# -MCU.net
KiCad netlist of a schematic drawn in Altium Designer
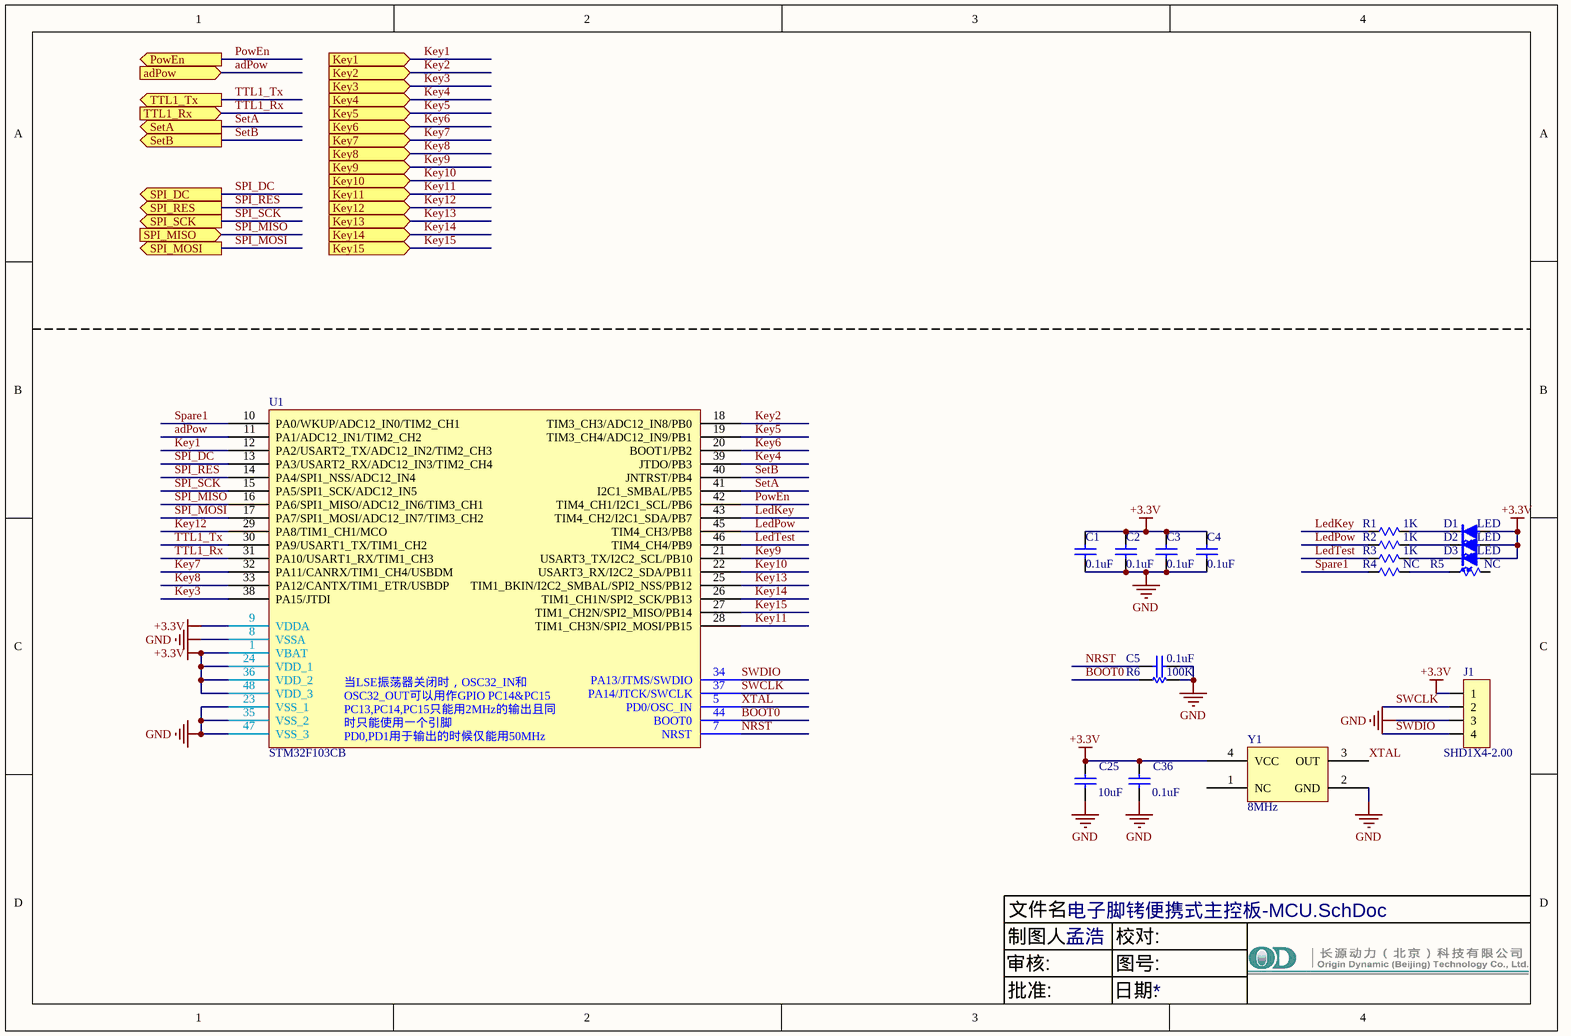
[diagram p0: 电子脚铐便携式主控板-MCU.SchDoc]

(export (version "E")
  (design (tool "Eeschema 10.0.6"))
  (components
    (comp (ref "C1") (value "0.1uF") (footprint "C0603") (libsource (lib "RLCYDF") (part "Cap Semi")))
    (comp (ref "C2") (value "0.1uF") (footprint "C0603") (libsource (lib "RLCYDF") (part "Cap Semi")))
    (comp (ref "C3") (value "0.1uF") (footprint "C0603") (libsource (lib "RLCYDF") (part "Cap Semi")))
    (comp (ref "C4") (value "0.1uF") (footprint "C0603") (libsource (lib "RLCYDF") (part "Cap Semi")))
    (comp (ref "C5") (value "0.1uF") (footprint "C0603") (libsource (lib "RLCYDF") (part "Cap Semi")))
    (comp (ref "C25") (value "10uF") (footprint "C0603") (libsource (lib "RLCYDF") (part "Cap Semi")))
    (comp (ref "C36") (value "0.1uF") (footprint "C0603") (libsource (lib "RLCYDF") (part "Cap Semi")))
    (comp (ref "D1")
      (value "LED")
      (footprint "LED0805")
      (libsource (lib "Passive Components Class") (part "LED"))
    )
    (comp (ref "D2")
      (value "LED")
      (footprint "LED0805")
      (libsource (lib "Passive Components Class") (part "LED"))
    )
    (comp (ref "D3")
      (value "LED")
      (footprint "LED0805")
      (libsource (lib "Passive Components Class") (part "LED"))
    )
    (comp (ref "J1")
      (value "SHD1X4-2.00")
      (footprint "Jk1*4-2.0")
      (libsource (lib "Connector Class") (part "HEADER1X4"))
    )
    (comp (ref "R1")
      (value "1K")
      (footprint "R0603")
      (description "Resistor")
      (fields (field (name "PUBLISHER") "Altium Limited"))
      (libsource (lib "UP-Robot") (part "Res"))
    )
    (comp (ref "R2")
      (value "1K")
      (footprint "R0603")
      (description "Resistor")
      (fields (field (name "PUBLISHER") "Altium Limited"))
      (libsource (lib "UP-Robot") (part "Res"))
    )
    (comp (ref "R3")
      (value "1K")
      (footprint "R0603")
      (description "Resistor")
      (fields (field (name "PUBLISHER") "Altium Limited"))
      (libsource (lib "UP-Robot") (part "Res"))
    )
    (comp (ref "R4")
      (value "NC")
      (footprint "R0603")
      (description "Resistor")
      (fields (field (name "PUBLISHER") "Altium Limited"))
      (libsource (lib "UP-Robot") (part "Res"))
    )
    (comp (ref "R5")
      (value "NC")
      (footprint "R0603")
      (description "Resistor")
      (fields (field (name "PUBLISHER") "Altium Limited"))
      (libsource (lib "UP-Robot") (part "Res"))
    )
    (comp (ref "R6") (value "100K") (footprint "R0603") (libsource (lib "RLCYDF") (part "Res")))
    (comp (ref "U1")
      (value "STM32F103CB")
      (footprint "LQFP48")
      (libsource (lib "stm32") (part "STM32F103Cx"))
    )
    (comp (ref "Y1")
      (value "8MHz")
      (footprint "XTAL5032")
      (description "SM crystal oscilator")
      (libsource (lib "RLCYDF") (part "XTAL"))
    )
  )
  (nets
    (net (code "1") (name "+3.3V") (class "Default")
      (node (ref "C1") (pin "1") (pinfunction "1_1") (pintype "passive"))
      (node (ref "C2") (pin "1") (pinfunction "1_1") (pintype "passive"))
      (node (ref "C25") (pin "2") (pinfunction "2_2") (pintype "passive"))
      (node (ref "C3") (pin "1") (pinfunction "1_1") (pintype "passive"))
      (node (ref "C36") (pin "2") (pinfunction "2_2") (pintype "passive"))
      (node (ref "C4") (pin "1") (pinfunction "1_1") (pintype "passive"))
      (node (ref "D1") (pin "1") (pinfunction "A_1") (pintype "passive"))
      (node (ref "D2") (pin "1") (pinfunction "A_1") (pintype "passive"))
      (node (ref "D3") (pin "1") (pinfunction "A_1") (pintype "passive"))
      (node (ref "J1") (pin "1") (pinfunction "1_1") (pintype "passive"))
      (node (ref "U1") (pin "1") (pinfunction "VBAT_1") (pintype "power_in"))
      (node (ref "U1") (pin "24") (pinfunction "VDD_1_24") (pintype "power_in"))
      (node (ref "U1") (pin "36") (pinfunction "VDD_2_36") (pintype "power_in"))
      (node (ref "U1") (pin "48") (pinfunction "VDD_3_48") (pintype "power_in"))
      (node (ref "U1") (pin "9") (pinfunction "VDDA_9") (pintype "power_in"))
      (node (ref "Y1") (pin "4") (pinfunction "VCC_4") (pintype "passive"))
    )
    (net (code "2") (name "/BOOT0") (class "Default")
      (node (ref "R6") (pin "1") (pinfunction "1_1") (pintype "passive"))
      (node (ref "U1") (pin "44") (pinfunction "BOOT0_44") (pintype "passive"))
    )
    (net (code "3") (name "/Key1") (class "Default")
      (node (ref "U1") (pin "12") (pinfunction "PA2/USART2_TX/ADC12_IN2/TIM2_CH3_12") (pintype "passive"))
    )
    (net (code "4") (name "/Key2") (class "Default")
      (node (ref "U1") (pin "18") (pinfunction "TIM3_CH3/ADC12_IN8/PB0_18") (pintype "passive"))
    )
    (net (code "5") (name "/Key3") (class "Default")
      (node (ref "U1") (pin "38") (pinfunction "PA15/JTDI_38") (pintype "passive"))
    )
    (net (code "6") (name "/Key4") (class "Default")
      (node (ref "U1") (pin "39") (pinfunction "JTDO/PB3_39") (pintype "passive"))
    )
    (net (code "7") (name "/Key5") (class "Default")
      (node (ref "U1") (pin "19") (pinfunction "TIM3_CH4/ADC12_IN9/PB1_19") (pintype "passive"))
    )
    (net (code "8") (name "/Key6") (class "Default")
      (node (ref "U1") (pin "20") (pinfunction "BOOT1/PB2_20") (pintype "passive"))
    )
    (net (code "9") (name "/Key7") (class "Default")
      (node (ref "U1") (pin "32") (pinfunction "PA11/CANRX/TIM1_CH4/USBDM_32") (pintype "passive"))
    )
    (net (code "10") (name "/Key8") (class "Default")
      (node (ref "U1") (pin "33") (pinfunction "PA12/CANTX/TIM1_ETR/USBDP_33") (pintype "passive"))
    )
    (net (code "11") (name "/Key9") (class "Default")
      (node (ref "U1") (pin "21") (pinfunction "USART3_TX/I2C2_SCL/PB10_21") (pintype "passive"))
    )
    (net (code "12") (name "/Key10") (class "Default")
      (node (ref "U1") (pin "22") (pinfunction "USART3_RX/I2C2_SDA/PB11_22") (pintype "passive"))
    )
    (net (code "13") (name "/Key11") (class "Default")
      (node (ref "U1") (pin "28") (pinfunction "TIM1_CH3N/SPI2_MOSI/PB15_28") (pintype "passive"))
    )
    (net (code "14") (name "/Key12") (class "Default")
      (node (ref "U1") (pin "29") (pinfunction "PA8/TIM1_CH1/MCO_29") (pintype "passive"))
    )
    (net (code "15") (name "/Key13") (class "Default")
      (node (ref "U1") (pin "25") (pinfunction "TIM1_BKIN/I2C2_SMBAL/SPI2_NSS/PB12_25") (pintype "passive"))
    )
    (net (code "16") (name "/Key14") (class "Default")
      (node (ref "U1") (pin "26") (pinfunction "TIM1_CH1N/SPI2_SCK/PB13_26") (pintype "passive"))
    )
    (net (code "17") (name "/Key15") (class "Default")
      (node (ref "U1") (pin "27") (pinfunction "TIM1_CH2N/SPI2_MISO/PB14_27") (pintype "passive"))
    )
    (net (code "18") (name "/LedKey") (class "Default")
      (node (ref "R1") (pin "2") (pinfunction "2_2") (pintype "passive"))
      (node (ref "U1") (pin "43") (pinfunction "TIM4_CH2/I2C1_SDA/PB7_43") (pintype "passive"))
    )
    (net (code "19") (name "/LedPow") (class "Default")
      (node (ref "R2") (pin "2") (pinfunction "2_2") (pintype "passive"))
      (node (ref "U1") (pin "45") (pinfunction "TIM4_CH3/PB8_45") (pintype "passive"))
    )
    (net (code "20") (name "/LedTest") (class "Default")
      (node (ref "R3") (pin "2") (pinfunction "2_2") (pintype "passive"))
      (node (ref "U1") (pin "46") (pinfunction "TIM4_CH4/PB9_46") (pintype "passive"))
    )
    (net (code "21") (name "/NRST") (class "Default")
      (node (ref "C5") (pin "1") (pinfunction "1_1") (pintype "passive"))
      (node (ref "U1") (pin "7") (pinfunction "NRST_7") (pintype "passive"))
    )
    (net (code "22") (name "/PowEn") (class "Default")
      (node (ref "U1") (pin "42") (pinfunction "TIM4_CH1/I2C1_SCL/PB6_42") (pintype "passive"))
    )
    (net (code "23") (name "/SPI_DC") (class "Default")
      (node (ref "U1") (pin "13") (pinfunction "PA3/USART2_RX/ADC12_IN3/TIM2_CH4_13") (pintype "passive"))
    )
    (net (code "24") (name "/SPI_MISO") (class "Default")
      (node (ref "U1") (pin "16") (pinfunction "PA6/SPI1_MISO/ADC12_IN6/TIM3_CH1_16") (pintype "passive"))
    )
    (net (code "25") (name "/SPI_MOSI") (class "Default")
      (node (ref "U1") (pin "17") (pinfunction "PA7/SPI1_MOSI/ADC12_IN7/TIM3_CH2_17") (pintype "passive"))
    )
    (net (code "26") (name "/SPI_RES") (class "Default")
      (node (ref "U1") (pin "14") (pinfunction "PA4/SPI1_NSS/ADC12_IN4_14") (pintype "passive"))
    )
    (net (code "27") (name "/SPI_SCK") (class "Default")
      (node (ref "U1") (pin "15") (pinfunction "PA5/SPI1_SCK/ADC12_IN5_15") (pintype "passive"))
    )
    (net (code "28") (name "/SWCLK") (class "Default")
      (node (ref "J1") (pin "2") (pinfunction "2_2") (pintype "passive"))
      (node (ref "U1") (pin "37") (pinfunction "PA14/JTCK/SWCLK_37") (pintype "passive"))
    )
    (net (code "29") (name "/SWDIO") (class "Default")
      (node (ref "J1") (pin "4") (pinfunction "4_4") (pintype "passive"))
      (node (ref "U1") (pin "34") (pinfunction "PA13/JTMS/SWDIO_34") (pintype "passive"))
    )
    (net (code "30") (name "/SetA") (class "Default")
      (node (ref "U1") (pin "41") (pinfunction "I2C1_SMBAL/PB5_41") (pintype "passive"))
    )
    (net (code "31") (name "/SetB") (class "Default")
      (node (ref "U1") (pin "40") (pinfunction "JNTRST/PB4_40") (pintype "passive"))
    )
    (net (code "32") (name "/Spare1") (class "Default")
      (node (ref "R4") (pin "2") (pinfunction "2_2") (pintype "passive"))
      (node (ref "U1") (pin "10") (pinfunction "PA0/WKUP/ADC12_IN0/TIM2_CH1_10") (pintype "passive"))
    )
    (net (code "33") (name "/TTL1_Rx") (class "Default")
      (node (ref "U1") (pin "31") (pinfunction "PA10/USART1_RX/TIM1_CH3_31") (pintype "passive"))
    )
    (net (code "34") (name "/TTL1_Tx") (class "Default")
      (node (ref "U1") (pin "30") (pinfunction "PA9/USART1_TX/TIM1_CH2_30") (pintype "passive"))
    )
    (net (code "35") (name "/XTAL") (class "Default")
      (node (ref "U1") (pin "5") (pinfunction "PD0/OSC_IN_5") (pintype "passive"))
      (node (ref "Y1") (pin "3") (pinfunction "OUT_3") (pintype "passive"))
    )
    (net (code "36") (name "/adPow") (class "Default")
      (node (ref "U1") (pin "11") (pinfunction "PA1/ADC12_IN1/TIM2_CH2_11") (pintype "passive"))
    )
    (net (code "37") (name "GND") (class "Default")
      (node (ref "C1") (pin "2") (pinfunction "2_2") (pintype "passive"))
      (node (ref "C2") (pin "2") (pinfunction "2_2") (pintype "passive"))
      (node (ref "C25") (pin "1") (pinfunction "1_1") (pintype "passive"))
      (node (ref "C3") (pin "2") (pinfunction "2_2") (pintype "passive"))
      (node (ref "C36") (pin "1") (pinfunction "1_1") (pintype "passive"))
      (node (ref "C4") (pin "2") (pinfunction "2_2") (pintype "passive"))
      (node (ref "C5") (pin "2") (pinfunction "2_2") (pintype "passive"))
      (node (ref "J1") (pin "3") (pinfunction "3_3") (pintype "passive"))
      (node (ref "R6") (pin "2") (pinfunction "2_2") (pintype "passive"))
      (node (ref "U1") (pin "23") (pinfunction "VSS_1_23") (pintype "power_in"))
      (node (ref "U1") (pin "35") (pinfunction "VSS_2_35") (pintype "power_in"))
      (node (ref "U1") (pin "47") (pinfunction "VSS_3_47") (pintype "power_in"))
      (node (ref "U1") (pin "8") (pinfunction "VSSA_8") (pintype "power_in"))
      (node (ref "Y1") (pin "2") (pinfunction "GND_2") (pintype "passive"))
    )
    (net (code "38") (name "Net-(D1-K)") (class "Default")
      (node (ref "D1") (pin "2") (pinfunction "K_2") (pintype "passive"))
      (node (ref "R1") (pin "1") (pinfunction "1_1") (pintype "passive"))
    )
    (net (code "39") (name "Net-(D2-K)") (class "Default")
      (node (ref "D2") (pin "2") (pinfunction "K_2") (pintype "passive"))
      (node (ref "R2") (pin "1") (pinfunction "1_1") (pintype "passive"))
    )
    (net (code "40") (name "Net-(D3-K)") (class "Default")
      (node (ref "D3") (pin "2") (pinfunction "K_2") (pintype "passive"))
      (node (ref "R3") (pin "1") (pinfunction "1_1") (pintype "passive"))
    )
    (net (code "41") (name "Net-(R4-Pad1)") (class "Default")
      (node (ref "R4") (pin "1") (pinfunction "1_1") (pintype "passive"))
      (node (ref "R5") (pin "2") (pinfunction "2_2") (pintype "passive"))
    )
    (net (code "42") (name "unconnected-(R5-Pad1)") (class "Default")
      (node (ref "R5") (pin "1") (pinfunction "1_1") (pintype "passive"))
    )
    (net (code "43") (name "unconnected-(U1-PC13-TAMPER-RTC-Pad2)") (class "Default")
      (node (ref "U1") (pin "2") (pinfunction "PC13-TAMPER-RTC_2") (pintype "passive"))
    )
    (net (code "44") (name "unconnected-(U1-PC14-OSC32_IN-Pad3)") (class "Default")
      (node (ref "U1") (pin "3") (pinfunction "PC14-OSC32_IN_3") (pintype "passive"))
    )
    (net (code "45") (name "unconnected-(U1-PC15-OSC32_OUT-Pad4)") (class "Default")
      (node (ref "U1") (pin "4") (pinfunction "PC15-OSC32_OUT_4") (pintype "passive"))
    )
    (net (code "46") (name "unconnected-(U1-PD1{slash}OSC_OUT-Pad6)") (class "Default")
      (node (ref "U1") (pin "6") (pinfunction "PD1/OSC_OUT_6") (pintype "passive"))
    )
    (net (code "47") (name "unconnected-(Y1-NC-Pad1)") (class "Default")
      (node (ref "Y1") (pin "1") (pinfunction "NC_1") (pintype "passive"))
    )
  )
)
